# CON2.net
KiCad netlist of a schematic drawn in Altium Designer
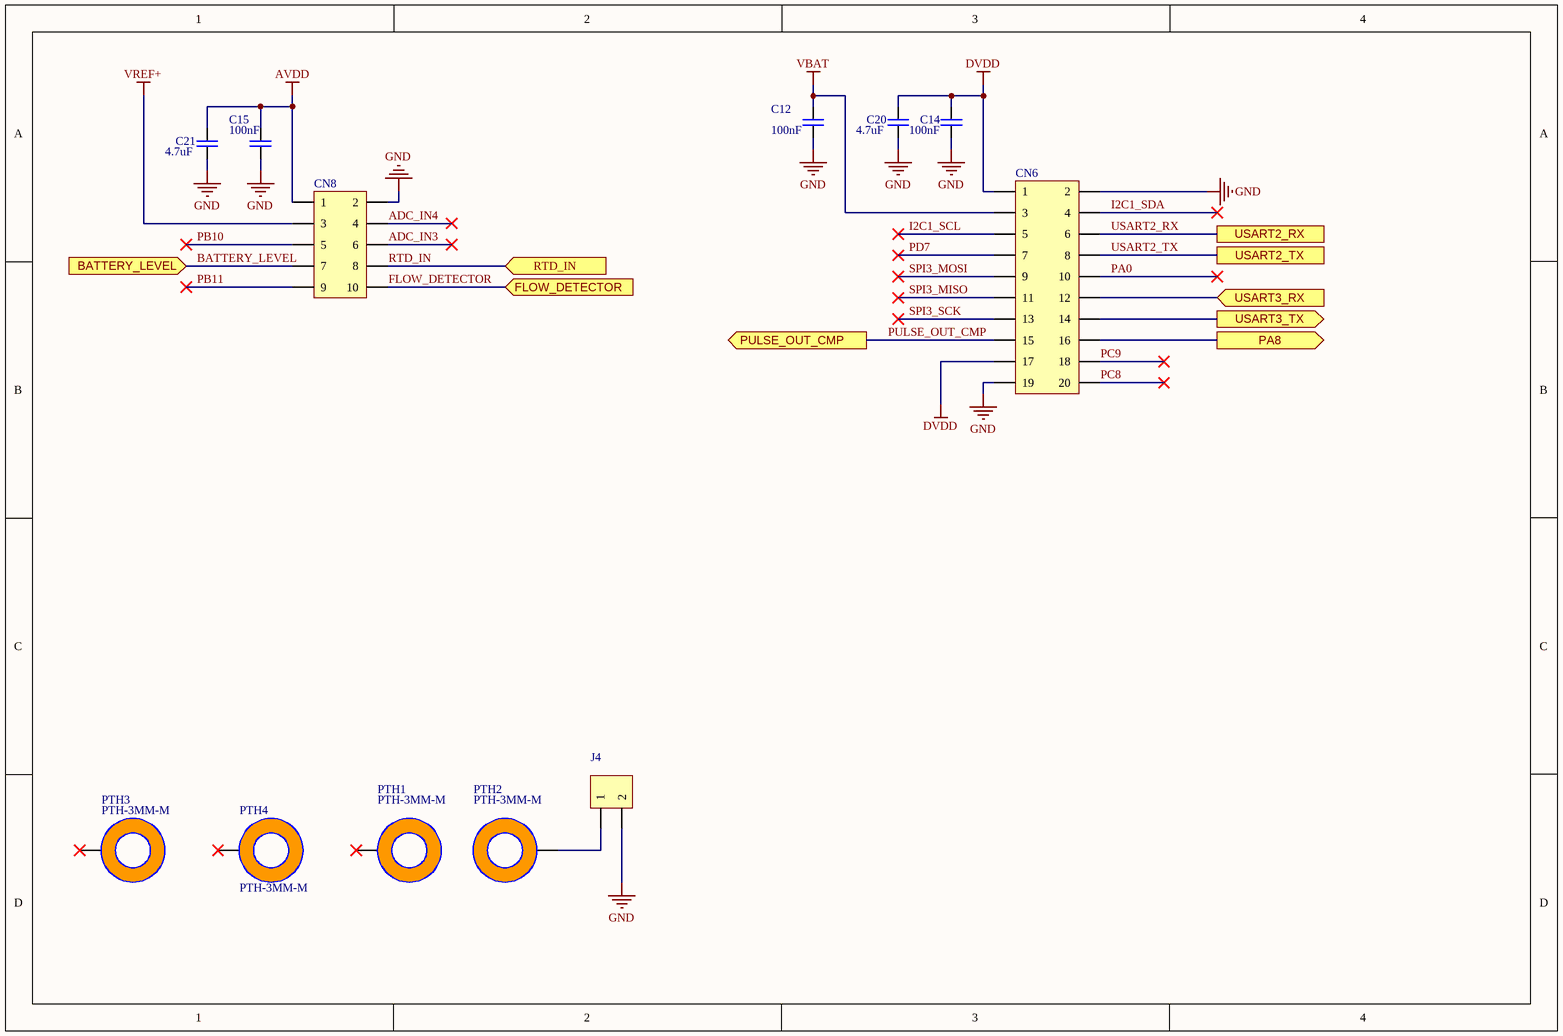
[diagram p0: CON2.SchDoc]

(export (version "E")
  (design (tool "Eeschema 10.0.6"))
  (components
    (comp (ref "C12")
      (value "100nF")
      (footprint "CAP_SM0805_YAGEOCC2_N")
      (description "CAP 100nF SM0805 X7R 25V YAGEO CC2")
      (fields
        (field (name "MANUFACTURER") "Yageo")
        (field (name "MANUFACTURER PART NUMBER") "CC0805KRX7R8BB104")
      )
      (libsource (lib "Yageo") (part "CC0805KRX7R8BB104"))
    )
    (comp (ref "C14")
      (value "100nF")
      (footprint "CAP_SM0805_YAGEOCC2_N")
      (description "CAP 100nF SM0805 X7R 25V YAGEO CC2")
      (fields
        (field (name "MANUFACTURER") "Yageo")
        (field (name "MANUFACTURER PART NUMBER") "CC0805KRX7R8BB104")
      )
      (libsource (lib "Yageo") (part "CC0805KRX7R8BB104"))
    )
    (comp (ref "C15")
      (value "100nF")
      (footprint "CAP_SM0805_YAGEOCC2_N")
      (description "CAP 100nF SM0805 X7R 25V YAGEO CC2")
      (fields
        (field (name "MANUFACTURER") "Yageo")
        (field (name "MANUFACTURER PART NUMBER") "CC0805KRX7R8BB104")
      )
      (libsource (lib "Yageo") (part "CC0805KRX7R8BB104"))
    )
    (comp (ref "C20")
      (value "4.7uF")
      (footprint "CAP_SM0805_YAGEOCC2_N")
      (description "CAP 4.7uF SM0805 X5R 10V YAGEO CC2")
      (fields
        (field (name "MANUFACTURER") "Yageo")
        (field (name "MANUFACTURER PART NUMBER") "CC0805KRX5R6BB475")
      )
      (libsource (lib "Yageo") (part "CC0805KRX5R6BB475"))
    )
    (comp (ref "C21")
      (value "4.7uF")
      (footprint "CAP_SM0805_YAGEOCC2_N")
      (description "CAP 4.7uF SM0805 X5R 10V YAGEO CC2")
      (fields
        (field (name "MANUFACTURER") "Yageo")
        (field (name "MANUFACTURER PART NUMBER") "CC0805KRX5R6BB475")
      )
      (libsource (lib "Yageo") (part "CC0805KRX5R6BB475"))
    )
    (comp (ref "CN6")
      (value "DZ254R-22-20-63")
      (footprint "HEADER PIN 2X10")
      (description "2 x 10 - true hole 2.54mm")
      (fields (field (name "MANUFACTURER") "DEALON"))
      (libsource (lib "header_pin") (part "DZ254R-22-20-63"))
    )
    (comp (ref "CN8")
      (value "Uar Equivalente")
      (footprint "HEADER PIN 2X5 MIRROR")
      (description "2 x 5 - true hole 2.54mm")
      (fields
        (field (name "MANUFACTURER") "DEALON")
        (field (name "MANUFACTURER PART NUMBER") "DZ254R-22-10-63")
      )
      (libsource (lib "header_pin") (part "DZ254R-22-10-63"))
    )
    (comp (ref "J4")
      (value "Usar Equivalene")
      (footprint "HEADER PIN 1X2")
      (description "1 x 2 - true hole  2.54mm - Pb free")
      (fields
        (field (name "MANUFACTURER") "Amphenol ICC")
        (field (name "MANUFACTURER PART NUMBER") "54101-T0602LF")
      )
      (libsource (lib "header_pin") (part "54101-T0602LF"))
    )
    (comp (ref "PTH1")
      (value "PTH-3MM-M")
      (footprint "PTH_M3_M")
      (description "Agujero de montaje metalizado roscas M3. Drill de tamaño medio.")
      (libsource (lib "montaje") (part "PTH-3MM-M"))
    )
    (comp (ref "PTH2")
      (value "PTH-3MM-M")
      (footprint "PTH_M3_M")
      (description "Agujero de montaje metalizado roscas M3. Drill de tamaño medio.")
      (libsource (lib "montaje") (part "PTH-3MM-M"))
    )
    (comp (ref "PTH3")
      (value "PTH-3MM-M")
      (footprint "PTH_M3_M")
      (description "Agujero de montaje metalizado roscas M3. Drill de tamaño medio.")
      (libsource (lib "montaje") (part "PTH-3MM-M"))
    )
    (comp (ref "PTH4")
      (value "PTH-3MM-M")
      (footprint "PTH_M3_M")
      (description "Agujero de montaje metalizado roscas M3. Drill de tamaño medio.")
      (libsource (lib "montaje") (part "PTH-3MM-M"))
    )
  )
  (nets
    (net (code "1") (name "/ADC_IN3") (class "Default")
      (node (ref "CN8") (pin "6") (pinfunction "6_6") (pintype "passive+no_connect"))
    )
    (net (code "2") (name "/ADC_IN4") (class "Default")
      (node (ref "CN8") (pin "4") (pinfunction "4_4") (pintype "passive+no_connect"))
    )
    (net (code "3") (name "/BATTERY_LEVEL") (class "Default")
      (node (ref "CN8") (pin "7") (pinfunction "7_7") (pintype "passive"))
    )
    (net (code "4") (name "/FLOW_DETECTOR") (class "Default")
      (node (ref "CN8") (pin "10") (pinfunction "10_10") (pintype "passive"))
    )
    (net (code "5") (name "/I2C1_SCL") (class "Default")
      (node (ref "CN6") (pin "5") (pinfunction "5_5") (pintype "passive+no_connect"))
    )
    (net (code "6") (name "/I2C1_SDA") (class "Default")
      (node (ref "CN6") (pin "4") (pinfunction "4_4") (pintype "passive+no_connect"))
    )
    (net (code "7") (name "/PA0") (class "Default")
      (node (ref "CN6") (pin "10") (pinfunction "10_10") (pintype "passive+no_connect"))
    )
    (net (code "8") (name "/PA8") (class "Default")
      (node (ref "CN6") (pin "16") (pinfunction "16_16") (pintype "passive"))
    )
    (net (code "9") (name "/PB10") (class "Default")
      (node (ref "CN8") (pin "5") (pinfunction "5_5") (pintype "passive+no_connect"))
    )
    (net (code "10") (name "/PB11") (class "Default")
      (node (ref "CN8") (pin "9") (pinfunction "9_9") (pintype "passive+no_connect"))
    )
    (net (code "11") (name "/PC8") (class "Default")
      (node (ref "CN6") (pin "20") (pinfunction "20_20") (pintype "passive+no_connect"))
    )
    (net (code "12") (name "/PC9") (class "Default")
      (node (ref "CN6") (pin "18") (pinfunction "18_18") (pintype "passive+no_connect"))
    )
    (net (code "13") (name "/PD7") (class "Default")
      (node (ref "CN6") (pin "7") (pinfunction "7_7") (pintype "passive+no_connect"))
    )
    (net (code "14") (name "/PULSE_OUT_CMP") (class "Default")
      (node (ref "CN6") (pin "15") (pinfunction "15_15") (pintype "passive"))
    )
    (net (code "15") (name "/RTD_IN") (class "Default")
      (node (ref "CN8") (pin "8") (pinfunction "8_8") (pintype "passive"))
    )
    (net (code "16") (name "/SPI3_MISO") (class "Default")
      (node (ref "CN6") (pin "11") (pinfunction "11_11") (pintype "passive+no_connect"))
    )
    (net (code "17") (name "/SPI3_MOSI") (class "Default")
      (node (ref "CN6") (pin "9") (pinfunction "9_9") (pintype "passive+no_connect"))
    )
    (net (code "18") (name "/SPI3_SCK") (class "Default")
      (node (ref "CN6") (pin "13") (pinfunction "13_13") (pintype "passive+no_connect"))
    )
    (net (code "19") (name "/USART2_RX") (class "Default")
      (node (ref "CN6") (pin "6") (pinfunction "6_6") (pintype "passive"))
    )
    (net (code "20") (name "/USART2_TX") (class "Default")
      (node (ref "CN6") (pin "8") (pinfunction "8_8") (pintype "passive"))
    )
    (net (code "21") (name "/USART3_RX") (class "Default")
      (node (ref "CN6") (pin "12") (pinfunction "12_12") (pintype "passive"))
    )
    (net (code "22") (name "/USART3_TX") (class "Default")
      (node (ref "CN6") (pin "14") (pinfunction "14_14") (pintype "passive"))
    )
    (net (code "23") (name "AVDD") (class "Default")
      (node (ref "C15") (pin "1") (pintype "passive"))
      (node (ref "C21") (pin "1") (pintype "passive"))
      (node (ref "CN8") (pin "1") (pinfunction "1_1") (pintype "passive"))
    )
    (net (code "24") (name "DVDD") (class "Default")
      (node (ref "C14") (pin "1") (pintype "passive"))
      (node (ref "C20") (pin "1") (pintype "passive"))
      (node (ref "CN6") (pin "1") (pinfunction "1_1") (pintype "passive"))
      (node (ref "CN6") (pin "17") (pinfunction "17_17") (pintype "passive"))
    )
    (net (code "25") (name "GND") (class "Default")
      (node (ref "C12") (pin "2") (pintype "passive"))
      (node (ref "C14") (pin "2") (pintype "passive"))
      (node (ref "C15") (pin "2") (pintype "passive"))
      (node (ref "C20") (pin "2") (pintype "passive"))
      (node (ref "C21") (pin "2") (pintype "passive"))
      (node (ref "CN6") (pin "19") (pinfunction "19_19") (pintype "passive"))
      (node (ref "CN6") (pin "2") (pinfunction "2_2") (pintype "passive"))
      (node (ref "CN8") (pin "2") (pinfunction "2_2") (pintype "passive"))
      (node (ref "J4") (pin "2") (pinfunction "2_2") (pintype "passive"))
    )
    (net (code "26") (name "Net-(J4-Pad1)") (class "Default")
      (node (ref "J4") (pin "1") (pinfunction "1_1") (pintype "passive"))
      (node (ref "PTH2") (pin "1") (pinfunction "1_1") (pintype "passive"))
    )
    (net (code "27") (name "VBAT") (class "Default")
      (node (ref "C12") (pin "1") (pintype "passive"))
      (node (ref "CN6") (pin "3") (pinfunction "3_3") (pintype "passive"))
    )
    (net (code "28") (name "VREF+") (class "Default")
      (node (ref "CN8") (pin "3") (pinfunction "3_3") (pintype "passive"))
    )
    (net (code "29") (name "unconnected-(PTH1-Pad1)") (class "Default")
      (node (ref "PTH1") (pin "1") (pinfunction "1_1") (pintype "passive+no_connect"))
    )
    (net (code "30") (name "unconnected-(PTH3-Pad1)") (class "Default")
      (node (ref "PTH3") (pin "1") (pinfunction "1_1") (pintype "passive+no_connect"))
    )
    (net (code "31") (name "unconnected-(PTH4-Pad1)") (class "Default")
      (node (ref "PTH4") (pin "1") (pinfunction "1_1") (pintype "passive+no_connect"))
    )
  )
)
